# MotorDriver.net
KiCad netlist of a schematic drawn in Altium Designer
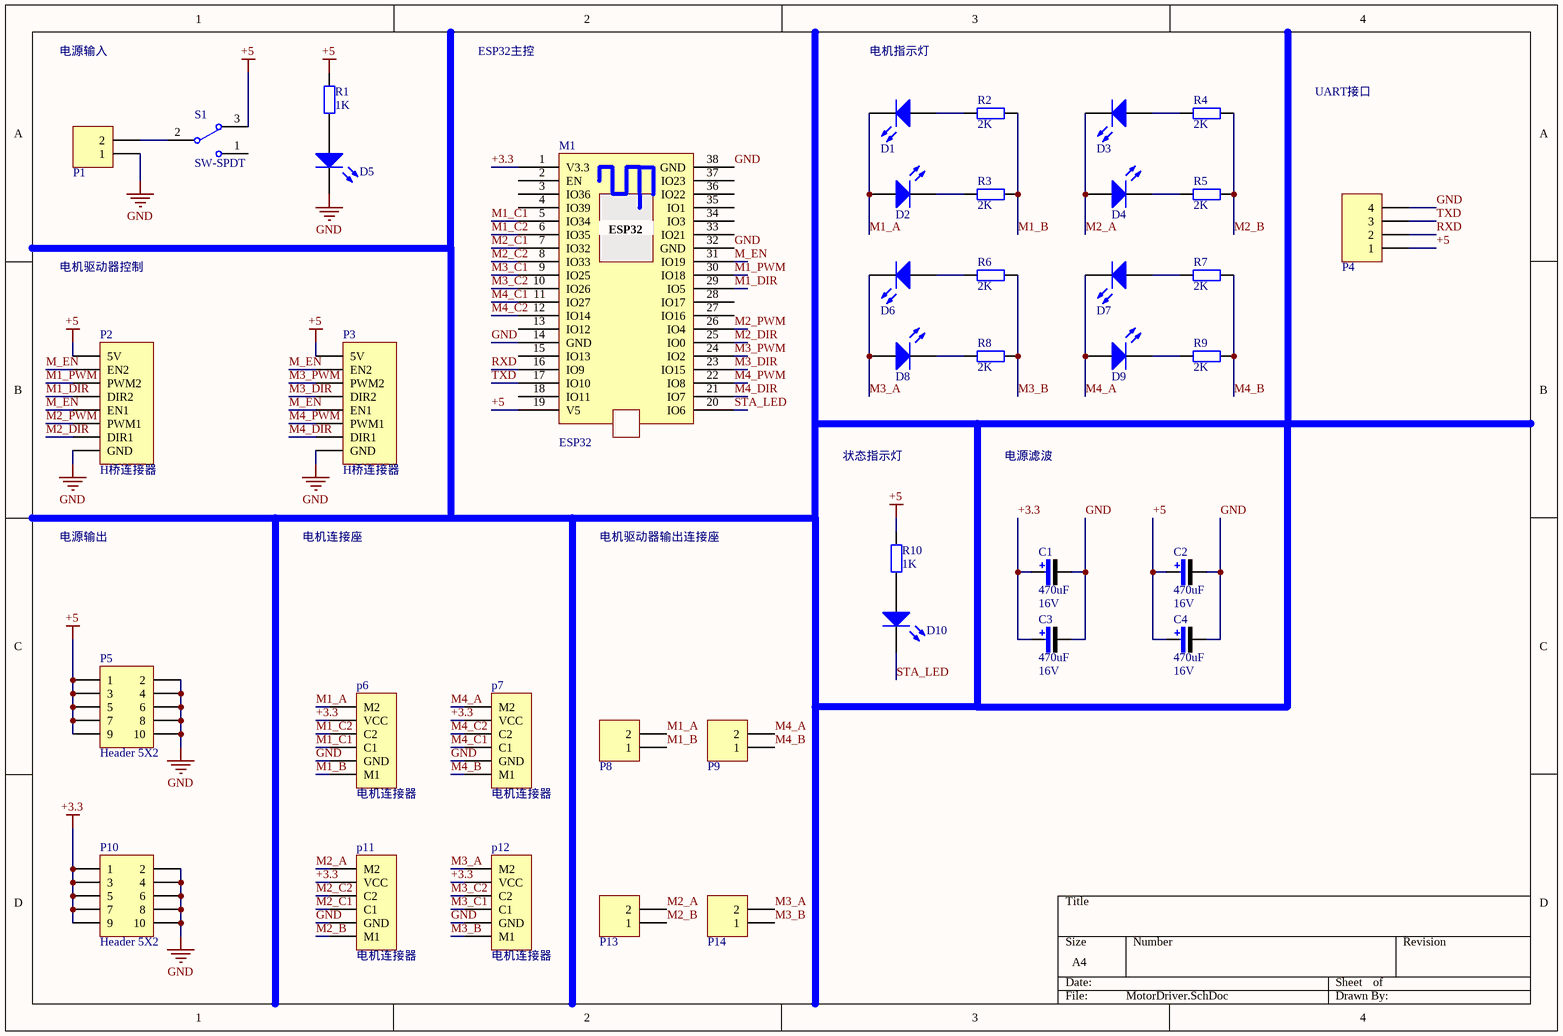
[diagram p0: MotorDriver.SchDoc]

(export (version "E")
  (design (tool "Eeschema 10.0.6"))
  (components
    (comp (ref "C1")
      (value "470uF")
      (footprint "C-RB-8")
      (description "极性电解电容")
      (fields
        (field (name "VOL") "16V")
        (field (name "Comment") "Cap Pol")
        (field (name "PUBLISHER") "Altium Limited")
      )
      (libsource (lib "主集成库_YP") (part "Cap Pol"))
    )
    (comp (ref "C2")
      (value "470uF")
      (footprint "C-RB-8")
      (description "极性电解电容")
      (fields
        (field (name "VOL") "16V")
        (field (name "Comment") "Cap Pol")
        (field (name "PUBLISHER") "Altium Limited")
      )
      (libsource (lib "主集成库_YP") (part "Cap Pol"))
    )
    (comp (ref "C3")
      (value "470uF")
      (footprint "C-RB-8")
      (description "极性电解电容")
      (fields
        (field (name "VOL") "16V")
        (field (name "Comment") "Cap Pol")
        (field (name "PUBLISHER") "Altium Limited")
      )
      (libsource (lib "主集成库_YP") (part "Cap Pol"))
    )
    (comp (ref "C4")
      (value "470uF")
      (footprint "C-RB-8")
      (description "极性电解电容")
      (fields
        (field (name "VOL") "16V")
        (field (name "Comment") "Cap Pol")
        (field (name "PUBLISHER") "Altium Limited")
      )
      (libsource (lib "主集成库_YP") (part "Cap Pol"))
    )
    (comp (ref "D1")
      (value "LED0")
      (footprint "LED_DIP")
      (description "发光二极管")
      (fields (field (name "PUBLISHER") "Altium Limited"))
      (libsource (lib "主集成库_YP") (part "LED0"))
    )
    (comp (ref "D2")
      (value "LED0")
      (footprint "LED_DIP")
      (description "发光二极管")
      (fields (field (name "PUBLISHER") "Altium Limited"))
      (libsource (lib "主集成库_YP") (part "LED0"))
    )
    (comp (ref "D3")
      (value "LED0")
      (footprint "LED_DIP")
      (description "发光二极管")
      (fields (field (name "PUBLISHER") "Altium Limited"))
      (libsource (lib "主集成库_YP") (part "LED0"))
    )
    (comp (ref "D4")
      (value "LED0")
      (footprint "LED_DIP")
      (description "发光二极管")
      (fields (field (name "PUBLISHER") "Altium Limited"))
      (libsource (lib "主集成库_YP") (part "LED0"))
    )
    (comp (ref "D5")
      (value "LED0")
      (footprint "LED_DIP")
      (description "发光二极管")
      (fields (field (name "PUBLISHER") "Altium Limited"))
      (libsource (lib "主集成库_YP") (part "LED0"))
    )
    (comp (ref "D6")
      (value "LED0")
      (footprint "LED_DIP")
      (description "发光二极管")
      (fields (field (name "PUBLISHER") "Altium Limited"))
      (libsource (lib "主集成库_YP") (part "LED0"))
    )
    (comp (ref "D7")
      (value "LED0")
      (footprint "LED_DIP")
      (description "发光二极管")
      (fields (field (name "PUBLISHER") "Altium Limited"))
      (libsource (lib "主集成库_YP") (part "LED0"))
    )
    (comp (ref "D8")
      (value "LED0")
      (footprint "LED_DIP")
      (description "发光二极管")
      (fields (field (name "PUBLISHER") "Altium Limited"))
      (libsource (lib "主集成库_YP") (part "LED0"))
    )
    (comp (ref "D9")
      (value "LED0")
      (footprint "LED_DIP")
      (description "发光二极管")
      (fields (field (name "PUBLISHER") "Altium Limited"))
      (libsource (lib "主集成库_YP") (part "LED0"))
    )
    (comp (ref "D10")
      (value "LED0")
      (footprint "LED_DIP")
      (description "发光二极管")
      (fields (field (name "PUBLISHER") "Altium Limited"))
      (libsource (lib "主集成库_YP") (part "LED0"))
    )
    (comp (ref "M1")
      (value "ESP32")
      (footprint "ESP32-DEVKIT-38")
      (description "ESP32开发板，38引脚")
      (libsource (lib "MotorDriver") (part "ESP32-DEVKIT-38"))
    )
    (comp (ref "P1")
      (value "Header 2")
      (footprint "HDR2X1_A")
      (description "接插件")
      (fields (field (name "PUBLISHER") "Altium Limited"))
      (libsource (lib "主集成库_YP") (part "Header 2"))
    )
    (comp (ref "P2")
      (value "H桥连接器")
      (footprint "HDR8-PH2.54")
      (description "两路H桥连接器")
      (libsource (lib "MotorDriver") (part "Driver_Connector"))
    )
    (comp (ref "P3")
      (value "H桥连接器")
      (footprint "HDR8-PH2.54")
      (description "两路H桥连接器")
      (libsource (lib "MotorDriver") (part "Driver_Connector"))
    )
    (comp (ref "P4")
      (value "Header 4")
      (footprint "HDR4X1_A")
      (description "接插件")
      (fields (field (name "PUBLISHER") "Altium Limited"))
      (libsource (lib "主集成库_YP") (part "Header 4"))
    )
    (comp (ref "P5")
      (value "Header 5X2")
      (footprint "HDR5X2_A1")
      (description "接插件")
      (fields (field (name "PUBLISHER") "Altium Limited"))
      (libsource (lib "主集成库_YP") (part "Header 5X2"))
    )
    (comp (ref "p6")
      (value "电机连接器")
      (footprint "HDR6-XH2.54")
      (description "编码直流电机连接器")
      (libsource (lib "MotorDriver") (part "Motor_Connector"))
    )
    (comp (ref "p7")
      (value "电机连接器")
      (footprint "HDR6-XH2.54")
      (description "编码直流电机连接器")
      (libsource (lib "MotorDriver") (part "Motor_Connector"))
    )
    (comp (ref "P8")
      (value "Header 2")
      (footprint "HDR2X1_A")
      (description "接插件")
      (fields (field (name "PUBLISHER") "Altium Limited"))
      (libsource (lib "主集成库_YP") (part "Header 2"))
    )
    (comp (ref "P9")
      (value "Header 2")
      (footprint "HDR2X1_A")
      (description "接插件")
      (fields (field (name "PUBLISHER") "Altium Limited"))
      (libsource (lib "主集成库_YP") (part "Header 2"))
    )
    (comp (ref "P10")
      (value "Header 5X2")
      (footprint "HDR5X2_A1")
      (description "接插件")
      (fields (field (name "PUBLISHER") "Altium Limited"))
      (libsource (lib "主集成库_YP") (part "Header 5X2"))
    )
    (comp (ref "p11")
      (value "电机连接器")
      (footprint "HDR6-XH2.54")
      (description "编码直流电机连接器")
      (libsource (lib "MotorDriver") (part "Motor_Connector"))
    )
    (comp (ref "p12")
      (value "电机连接器")
      (footprint "HDR6-XH2.54")
      (description "编码直流电机连接器")
      (libsource (lib "MotorDriver") (part "Motor_Connector"))
    )
    (comp (ref "P13")
      (value "Header 2")
      (footprint "HDR2X1_A")
      (description "接插件")
      (fields (field (name "PUBLISHER") "Altium Limited"))
      (libsource (lib "主集成库_YP") (part "Header 2"))
    )
    (comp (ref "P14")
      (value "Header 2")
      (footprint "HDR2X1_A")
      (description "接插件")
      (fields (field (name "PUBLISHER") "Altium Limited"))
      (libsource (lib "主集成库_YP") (part "Header 2"))
    )
    (comp (ref "R1")
      (value "1K")
      (footprint "0603-1")
      (description "贴片电阻")
      (fields (field (name "Comment") "Res1") (field (name "PUBLISHER") "Altium Limited"))
      (libsource (lib "主集成库_YP") (part "Res1"))
    )
    (comp (ref "R2")
      (value "2K")
      (footprint "0603-1")
      (description "贴片电阻")
      (fields (field (name "Comment") "Res1") (field (name "PUBLISHER") "Altium Limited"))
      (libsource (lib "") (part "Res1_1"))
    )
    (comp (ref "R3")
      (value "2K")
      (footprint "0603-1")
      (description "贴片电阻")
      (fields (field (name "Comment") "Res1") (field (name "PUBLISHER") "Altium Limited"))
      (libsource (lib "") (part "Res1_1"))
    )
    (comp (ref "R4")
      (value "2K")
      (footprint "0603-1")
      (description "贴片电阻")
      (fields (field (name "Comment") "Res1") (field (name "PUBLISHER") "Altium Limited"))
      (libsource (lib "") (part "Res1_1"))
    )
    (comp (ref "R5")
      (value "2K")
      (footprint "0603-1")
      (description "贴片电阻")
      (fields (field (name "Comment") "Res1") (field (name "PUBLISHER") "Altium Limited"))
      (libsource (lib "") (part "Res1_1"))
    )
    (comp (ref "R6")
      (value "2K")
      (footprint "0603-1")
      (description "贴片电阻")
      (fields (field (name "Comment") "Res1") (field (name "PUBLISHER") "Altium Limited"))
      (libsource (lib "") (part "Res1_1"))
    )
    (comp (ref "R7")
      (value "2K")
      (footprint "0603-1")
      (description "贴片电阻")
      (fields (field (name "Comment") "Res1") (field (name "PUBLISHER") "Altium Limited"))
      (libsource (lib "") (part "Res1_1"))
    )
    (comp (ref "R8")
      (value "2K")
      (footprint "0603-1")
      (description "贴片电阻")
      (fields (field (name "Comment") "Res1") (field (name "PUBLISHER") "Altium Limited"))
      (libsource (lib "") (part "Res1_1"))
    )
    (comp (ref "R9")
      (value "2K")
      (footprint "0603-1")
      (description "贴片电阻")
      (fields (field (name "Comment") "Res1") (field (name "PUBLISHER") "Altium Limited"))
      (libsource (lib "") (part "Res1_1"))
    )
    (comp (ref "R10")
      (value "1K")
      (footprint "0603-1")
      (description "贴片电阻")
      (fields (field (name "Comment") "Res1") (field (name "PUBLISHER") "Altium Limited"))
      (libsource (lib "主集成库_YP") (part "Res1"))
    )
    (comp (ref "S1")
      (value "SW-SPDT")
      (footprint "SWITCH_A1")
      (description "开关")
      (fields (field (name "PUBLISHER") "Altium Limited"))
      (libsource (lib "主集成库_YP") (part "SW-SPDT"))
    )
  )
  (nets
    (net (code "1") (name "+3.3") (class "Default")
      (node (ref "C1") (pin "1") (pinfunction "1_1") (pintype "passive"))
      (node (ref "C3") (pin "1") (pinfunction "1_1") (pintype "passive"))
      (node (ref "M1") (pin "1") (pinfunction "V3.3_1") (pintype "passive"))
      (node (ref "P10") (pin "1") (pinfunction "1_1") (pintype "passive"))
      (node (ref "P10") (pin "3") (pinfunction "3_3") (pintype "passive"))
      (node (ref "P10") (pin "5") (pinfunction "5_5") (pintype "passive"))
      (node (ref "P10") (pin "7") (pinfunction "7_7") (pintype "passive"))
      (node (ref "P10") (pin "9") (pinfunction "9_9") (pintype "passive"))
      (node (ref "p11") (pin "2") (pinfunction "VCC_2") (pintype "passive"))
      (node (ref "p12") (pin "2") (pinfunction "VCC_2") (pintype "passive"))
      (node (ref "p6") (pin "2") (pinfunction "VCC_2") (pintype "passive"))
      (node (ref "p7") (pin "2") (pinfunction "VCC_2") (pintype "passive"))
    )
    (net (code "2") (name "+5") (class "Default")
      (node (ref "C2") (pin "1") (pinfunction "1_1") (pintype "passive"))
      (node (ref "C4") (pin "1") (pinfunction "1_1") (pintype "passive"))
      (node (ref "M1") (pin "19") (pinfunction "V5_19") (pintype "passive"))
      (node (ref "P2") (pin "1") (pinfunction "5V_1") (pintype "passive"))
      (node (ref "P3") (pin "1") (pinfunction "5V_1") (pintype "passive"))
      (node (ref "P4") (pin "1") (pinfunction "1_1") (pintype "passive"))
      (node (ref "P5") (pin "1") (pinfunction "1_1") (pintype "passive"))
      (node (ref "P5") (pin "3") (pinfunction "3_3") (pintype "passive"))
      (node (ref "P5") (pin "5") (pinfunction "5_5") (pintype "passive"))
      (node (ref "P5") (pin "7") (pinfunction "7_7") (pintype "passive"))
      (node (ref "P5") (pin "9") (pinfunction "9_9") (pintype "passive"))
      (node (ref "R1") (pin "2") (pinfunction "2_2") (pintype "passive"))
      (node (ref "R10") (pin "2") (pinfunction "2_2") (pintype "passive"))
      (node (ref "S1") (pin "3") (pinfunction "3_3") (pintype "passive"))
    )
    (net (code "3") (name "/M1_A") (class "Default")
      (node (ref "D1") (pin "2") (pinfunction "K_2") (pintype "passive"))
      (node (ref "D2") (pin "1") (pinfunction "A_1") (pintype "passive"))
      (node (ref "P8") (pin "2") (pinfunction "2_2") (pintype "passive"))
      (node (ref "p6") (pin "1") (pinfunction "M2_1") (pintype "passive"))
    )
    (net (code "4") (name "/M1_B") (class "Default")
      (node (ref "P8") (pin "1") (pinfunction "1_1") (pintype "passive"))
      (node (ref "R2") (pin "2") (pinfunction "2_2") (pintype "passive"))
      (node (ref "R3") (pin "2") (pinfunction "2_2") (pintype "passive"))
      (node (ref "p6") (pin "6") (pinfunction "M1_6") (pintype "passive"))
    )
    (net (code "5") (name "/M1_C1") (class "Default")
      (node (ref "M1") (pin "5") (pinfunction "IO34_5") (pintype "passive"))
      (node (ref "p6") (pin "4") (pinfunction "C1_4") (pintype "passive"))
    )
    (net (code "6") (name "/M1_C2") (class "Default")
      (node (ref "M1") (pin "6") (pinfunction "IO35_6") (pintype "passive"))
      (node (ref "p6") (pin "3") (pinfunction "C2_3") (pintype "passive"))
    )
    (net (code "7") (name "/M1_DIR") (class "Default")
      (node (ref "M1") (pin "29") (pinfunction "IO5_29") (pintype "passive"))
      (node (ref "P2") (pin "4") (pinfunction "DIR2_4") (pintype "passive"))
    )
    (net (code "8") (name "/M1_PWM") (class "Default")
      (node (ref "M1") (pin "30") (pinfunction "IO18_30") (pintype "passive"))
      (node (ref "P2") (pin "3") (pinfunction "PWM2_3") (pintype "passive"))
    )
    (net (code "9") (name "/M2_A") (class "Default")
      (node (ref "D3") (pin "2") (pinfunction "K_2") (pintype "passive"))
      (node (ref "D4") (pin "1") (pinfunction "A_1") (pintype "passive"))
      (node (ref "P13") (pin "2") (pinfunction "2_2") (pintype "passive"))
      (node (ref "p11") (pin "1") (pinfunction "M2_1") (pintype "passive"))
    )
    (net (code "10") (name "/M2_B") (class "Default")
      (node (ref "P13") (pin "1") (pinfunction "1_1") (pintype "passive"))
      (node (ref "R4") (pin "2") (pinfunction "2_2") (pintype "passive"))
      (node (ref "R5") (pin "2") (pinfunction "2_2") (pintype "passive"))
      (node (ref "p11") (pin "6") (pinfunction "M1_6") (pintype "passive"))
    )
    (net (code "11") (name "/M2_C1") (class "Default")
      (node (ref "M1") (pin "7") (pinfunction "IO32_7") (pintype "passive"))
      (node (ref "p11") (pin "4") (pinfunction "C1_4") (pintype "passive"))
    )
    (net (code "12") (name "/M2_C2") (class "Default")
      (node (ref "M1") (pin "8") (pinfunction "IO33_8") (pintype "passive"))
      (node (ref "p11") (pin "3") (pinfunction "C2_3") (pintype "passive"))
    )
    (net (code "13") (name "/M2_DIR") (class "Default")
      (node (ref "M1") (pin "25") (pinfunction "IO0_25") (pintype "passive"))
      (node (ref "P2") (pin "7") (pinfunction "DIR1_7") (pintype "passive"))
    )
    (net (code "14") (name "/M2_PWM") (class "Default")
      (node (ref "M1") (pin "26") (pinfunction "IO4_26") (pintype "passive"))
      (node (ref "P2") (pin "6") (pinfunction "PWM1_6") (pintype "passive"))
    )
    (net (code "15") (name "/M3_A") (class "Default")
      (node (ref "D6") (pin "2") (pinfunction "K_2") (pintype "passive"))
      (node (ref "D8") (pin "1") (pinfunction "A_1") (pintype "passive"))
      (node (ref "P14") (pin "2") (pinfunction "2_2") (pintype "passive"))
      (node (ref "p12") (pin "1") (pinfunction "M2_1") (pintype "passive"))
    )
    (net (code "16") (name "/M3_B") (class "Default")
      (node (ref "P14") (pin "1") (pinfunction "1_1") (pintype "passive"))
      (node (ref "R6") (pin "2") (pinfunction "2_2") (pintype "passive"))
      (node (ref "R8") (pin "2") (pinfunction "2_2") (pintype "passive"))
      (node (ref "p12") (pin "6") (pinfunction "M1_6") (pintype "passive"))
    )
    (net (code "17") (name "/M3_C1") (class "Default")
      (node (ref "M1") (pin "9") (pinfunction "IO25_9") (pintype "passive"))
      (node (ref "p12") (pin "4") (pinfunction "C1_4") (pintype "passive"))
    )
    (net (code "18") (name "/M3_C2") (class "Default")
      (node (ref "M1") (pin "10") (pinfunction "IO26_10") (pintype "passive"))
      (node (ref "p12") (pin "3") (pinfunction "C2_3") (pintype "passive"))
    )
    (net (code "19") (name "/M3_DIR") (class "Default")
      (node (ref "M1") (pin "23") (pinfunction "IO15_23") (pintype "passive"))
      (node (ref "P3") (pin "4") (pinfunction "DIR2_4") (pintype "passive"))
    )
    (net (code "20") (name "/M3_PWM") (class "Default")
      (node (ref "M1") (pin "24") (pinfunction "IO2_24") (pintype "passive"))
      (node (ref "P3") (pin "3") (pinfunction "PWM2_3") (pintype "passive"))
    )
    (net (code "21") (name "/M4_A") (class "Default")
      (node (ref "D7") (pin "2") (pinfunction "K_2") (pintype "passive"))
      (node (ref "D9") (pin "1") (pinfunction "A_1") (pintype "passive"))
      (node (ref "P9") (pin "2") (pinfunction "2_2") (pintype "passive"))
      (node (ref "p7") (pin "1") (pinfunction "M2_1") (pintype "passive"))
    )
    (net (code "22") (name "/M4_B") (class "Default")
      (node (ref "P9") (pin "1") (pinfunction "1_1") (pintype "passive"))
      (node (ref "R7") (pin "2") (pinfunction "2_2") (pintype "passive"))
      (node (ref "R9") (pin "2") (pinfunction "2_2") (pintype "passive"))
      (node (ref "p7") (pin "6") (pinfunction "M1_6") (pintype "passive"))
    )
    (net (code "23") (name "/M4_C1") (class "Default")
      (node (ref "M1") (pin "11") (pinfunction "IO27_11") (pintype "passive"))
      (node (ref "p7") (pin "4") (pinfunction "C1_4") (pintype "passive"))
    )
    (net (code "24") (name "/M4_C2") (class "Default")
      (node (ref "M1") (pin "12") (pinfunction "IO14_12") (pintype "passive"))
      (node (ref "p7") (pin "3") (pinfunction "C2_3") (pintype "passive"))
    )
    (net (code "25") (name "/M4_DIR") (class "Default")
      (node (ref "M1") (pin "21") (pinfunction "IO7_21") (pintype "passive"))
      (node (ref "P3") (pin "7") (pinfunction "DIR1_7") (pintype "passive"))
    )
    (net (code "26") (name "/M4_PWM") (class "Default")
      (node (ref "M1") (pin "22") (pinfunction "IO8_22") (pintype "passive"))
      (node (ref "P3") (pin "6") (pinfunction "PWM1_6") (pintype "passive"))
    )
    (net (code "27") (name "/M_EN") (class "Default")
      (node (ref "M1") (pin "31") (pinfunction "IO19_31") (pintype "passive"))
      (node (ref "P2") (pin "2") (pinfunction "EN2_2") (pintype "passive"))
      (node (ref "P2") (pin "5") (pinfunction "EN1_5") (pintype "passive"))
      (node (ref "P3") (pin "2") (pinfunction "EN2_2") (pintype "passive"))
      (node (ref "P3") (pin "5") (pinfunction "EN1_5") (pintype "passive"))
    )
    (net (code "28") (name "/RXD") (class "Default")
      (node (ref "M1") (pin "16") (pinfunction "IO9_16") (pintype "passive"))
      (node (ref "P4") (pin "2") (pinfunction "2_2") (pintype "passive"))
    )
    (net (code "29") (name "/STA_LED") (class "Default")
      (node (ref "D10") (pin "2") (pinfunction "K_2") (pintype "passive"))
      (node (ref "M1") (pin "20") (pinfunction "IO6_20") (pintype "passive"))
    )
    (net (code "30") (name "/TXD") (class "Default")
      (node (ref "M1") (pin "17") (pinfunction "IO10_17") (pintype "passive"))
      (node (ref "P4") (pin "3") (pinfunction "3_3") (pintype "passive"))
    )
    (net (code "31") (name "GND") (class "Default")
      (node (ref "C1") (pin "2") (pinfunction "2_2") (pintype "passive"))
      (node (ref "C2") (pin "2") (pinfunction "2_2") (pintype "passive"))
      (node (ref "C3") (pin "2") (pinfunction "2_2") (pintype "passive"))
      (node (ref "C4") (pin "2") (pinfunction "2_2") (pintype "passive"))
      (node (ref "D5") (pin "2") (pinfunction "K_2") (pintype "passive"))
      (node (ref "M1") (pin "14") (pinfunction "GND_14") (pintype "passive"))
      (node (ref "M1") (pin "32") (pinfunction "GND_32") (pintype "passive"))
      (node (ref "M1") (pin "38") (pinfunction "GND_38") (pintype "passive"))
      (node (ref "P1") (pin "1") (pinfunction "1_1") (pintype "passive"))
      (node (ref "P10") (pin "10") (pinfunction "10_10") (pintype "passive"))
      (node (ref "P10") (pin "2") (pinfunction "2_2") (pintype "passive"))
      (node (ref "P10") (pin "4") (pinfunction "4_4") (pintype "passive"))
      (node (ref "P10") (pin "6") (pinfunction "6_6") (pintype "passive"))
      (node (ref "P10") (pin "8") (pinfunction "8_8") (pintype "passive"))
      (node (ref "P2") (pin "8") (pinfunction "GND_8") (pintype "passive"))
      (node (ref "P3") (pin "8") (pinfunction "GND_8") (pintype "passive"))
      (node (ref "P4") (pin "4") (pinfunction "4_4") (pintype "passive"))
      (node (ref "P5") (pin "10") (pinfunction "10_10") (pintype "passive"))
      (node (ref "P5") (pin "2") (pinfunction "2_2") (pintype "passive"))
      (node (ref "P5") (pin "4") (pinfunction "4_4") (pintype "passive"))
      (node (ref "P5") (pin "6") (pinfunction "6_6") (pintype "passive"))
      (node (ref "P5") (pin "8") (pinfunction "8_8") (pintype "passive"))
      (node (ref "p11") (pin "5") (pinfunction "GND_5") (pintype "passive"))
      (node (ref "p12") (pin "5") (pinfunction "GND_5") (pintype "passive"))
      (node (ref "p6") (pin "5") (pinfunction "GND_5") (pintype "passive"))
      (node (ref "p7") (pin "5") (pinfunction "GND_5") (pintype "passive"))
    )
    (net (code "32") (name "Net-(D1-A)") (class "Default")
      (node (ref "D1") (pin "1") (pinfunction "A_1") (pintype "passive"))
      (node (ref "R2") (pin "1") (pinfunction "1_1") (pintype "passive"))
    )
    (net (code "33") (name "Net-(D2-K)") (class "Default")
      (node (ref "D2") (pin "2") (pinfunction "K_2") (pintype "passive"))
      (node (ref "R3") (pin "1") (pinfunction "1_1") (pintype "passive"))
    )
    (net (code "34") (name "Net-(D3-A)") (class "Default")
      (node (ref "D3") (pin "1") (pinfunction "A_1") (pintype "passive"))
      (node (ref "R4") (pin "1") (pinfunction "1_1") (pintype "passive"))
    )
    (net (code "35") (name "Net-(D4-K)") (class "Default")
      (node (ref "D4") (pin "2") (pinfunction "K_2") (pintype "passive"))
      (node (ref "R5") (pin "1") (pinfunction "1_1") (pintype "passive"))
    )
    (net (code "36") (name "Net-(D5-A)") (class "Default")
      (node (ref "D5") (pin "1") (pinfunction "A_1") (pintype "passive"))
      (node (ref "R1") (pin "1") (pinfunction "1_1") (pintype "passive"))
    )
    (net (code "37") (name "Net-(D6-A)") (class "Default")
      (node (ref "D6") (pin "1") (pinfunction "A_1") (pintype "passive"))
      (node (ref "R6") (pin "1") (pinfunction "1_1") (pintype "passive"))
    )
    (net (code "38") (name "Net-(D7-A)") (class "Default")
      (node (ref "D7") (pin "1") (pinfunction "A_1") (pintype "passive"))
      (node (ref "R7") (pin "1") (pinfunction "1_1") (pintype "passive"))
    )
    (net (code "39") (name "Net-(D8-K)") (class "Default")
      (node (ref "D8") (pin "2") (pinfunction "K_2") (pintype "passive"))
      (node (ref "R8") (pin "1") (pinfunction "1_1") (pintype "passive"))
    )
    (net (code "40") (name "Net-(D9-K)") (class "Default")
      (node (ref "D9") (pin "2") (pinfunction "K_2") (pintype "passive"))
      (node (ref "R9") (pin "1") (pinfunction "1_1") (pintype "passive"))
    )
    (net (code "41") (name "Net-(D10-A)") (class "Default")
      (node (ref "D10") (pin "1") (pinfunction "A_1") (pintype "passive"))
      (node (ref "R10") (pin "1") (pinfunction "1_1") (pintype "passive"))
    )
    (net (code "42") (name "Net-(P1-Pad2)") (class "Default")
      (node (ref "P1") (pin "2") (pinfunction "2_2") (pintype "passive"))
      (node (ref "S1") (pin "2") (pinfunction "2_2") (pintype "passive"))
    )
    (net (code "43") (name "unconnected-(M1-EN-Pad2)") (class "Default")
      (node (ref "M1") (pin "2") (pinfunction "EN_2") (pintype "passive"))
    )
    (net (code "44") (name "unconnected-(M1-IO1-Pad35)") (class "Default")
      (node (ref "M1") (pin "35") (pinfunction "IO1_35") (pintype "passive"))
    )
    (net (code "45") (name "unconnected-(M1-IO3-Pad34)") (class "Default")
      (node (ref "M1") (pin "34") (pinfunction "IO3_34") (pintype "passive"))
    )
    (net (code "46") (name "unconnected-(M1-IO11-Pad18)") (class "Default")
      (node (ref "M1") (pin "18") (pinfunction "IO11_18") (pintype "passive"))
    )
    (net (code "47") (name "unconnected-(M1-IO12-Pad13)") (class "Default")
      (node (ref "M1") (pin "13") (pinfunction "IO12_13") (pintype "passive"))
    )
    (net (code "48") (name "unconnected-(M1-IO13-Pad15)") (class "Default")
      (node (ref "M1") (pin "15") (pinfunction "IO13_15") (pintype "passive"))
    )
    (net (code "49") (name "unconnected-(M1-IO16-Pad27)") (class "Default")
      (node (ref "M1") (pin "27") (pinfunction "IO16_27") (pintype "passive"))
    )
    (net (code "50") (name "unconnected-(M1-IO17-Pad28)") (class "Default")
      (node (ref "M1") (pin "28") (pinfunction "IO17_28") (pintype "passive"))
    )
    (net (code "51") (name "unconnected-(M1-IO21-Pad33)") (class "Default")
      (node (ref "M1") (pin "33") (pinfunction "IO21_33") (pintype "passive"))
    )
    (net (code "52") (name "unconnected-(M1-IO22-Pad36)") (class "Default")
      (node (ref "M1") (pin "36") (pinfunction "IO22_36") (pintype "passive"))
    )
    (net (code "53") (name "unconnected-(M1-IO23-Pad37)") (class "Default")
      (node (ref "M1") (pin "37") (pinfunction "IO23_37") (pintype "passive"))
    )
    (net (code "54") (name "unconnected-(M1-IO36-Pad3)") (class "Default")
      (node (ref "M1") (pin "3") (pinfunction "IO36_3") (pintype "passive"))
    )
    (net (code "55") (name "unconnected-(M1-IO39-Pad4)") (class "Default")
      (node (ref "M1") (pin "4") (pinfunction "IO39_4") (pintype "passive"))
    )
    (net (code "56") (name "unconnected-(S1-Pad1)") (class "Default")
      (node (ref "S1") (pin "1") (pinfunction "1_1") (pintype "passive"))
    )
  )
)
